# LPDDR3.net
KiCad netlist of a schematic drawn in Altium Designer
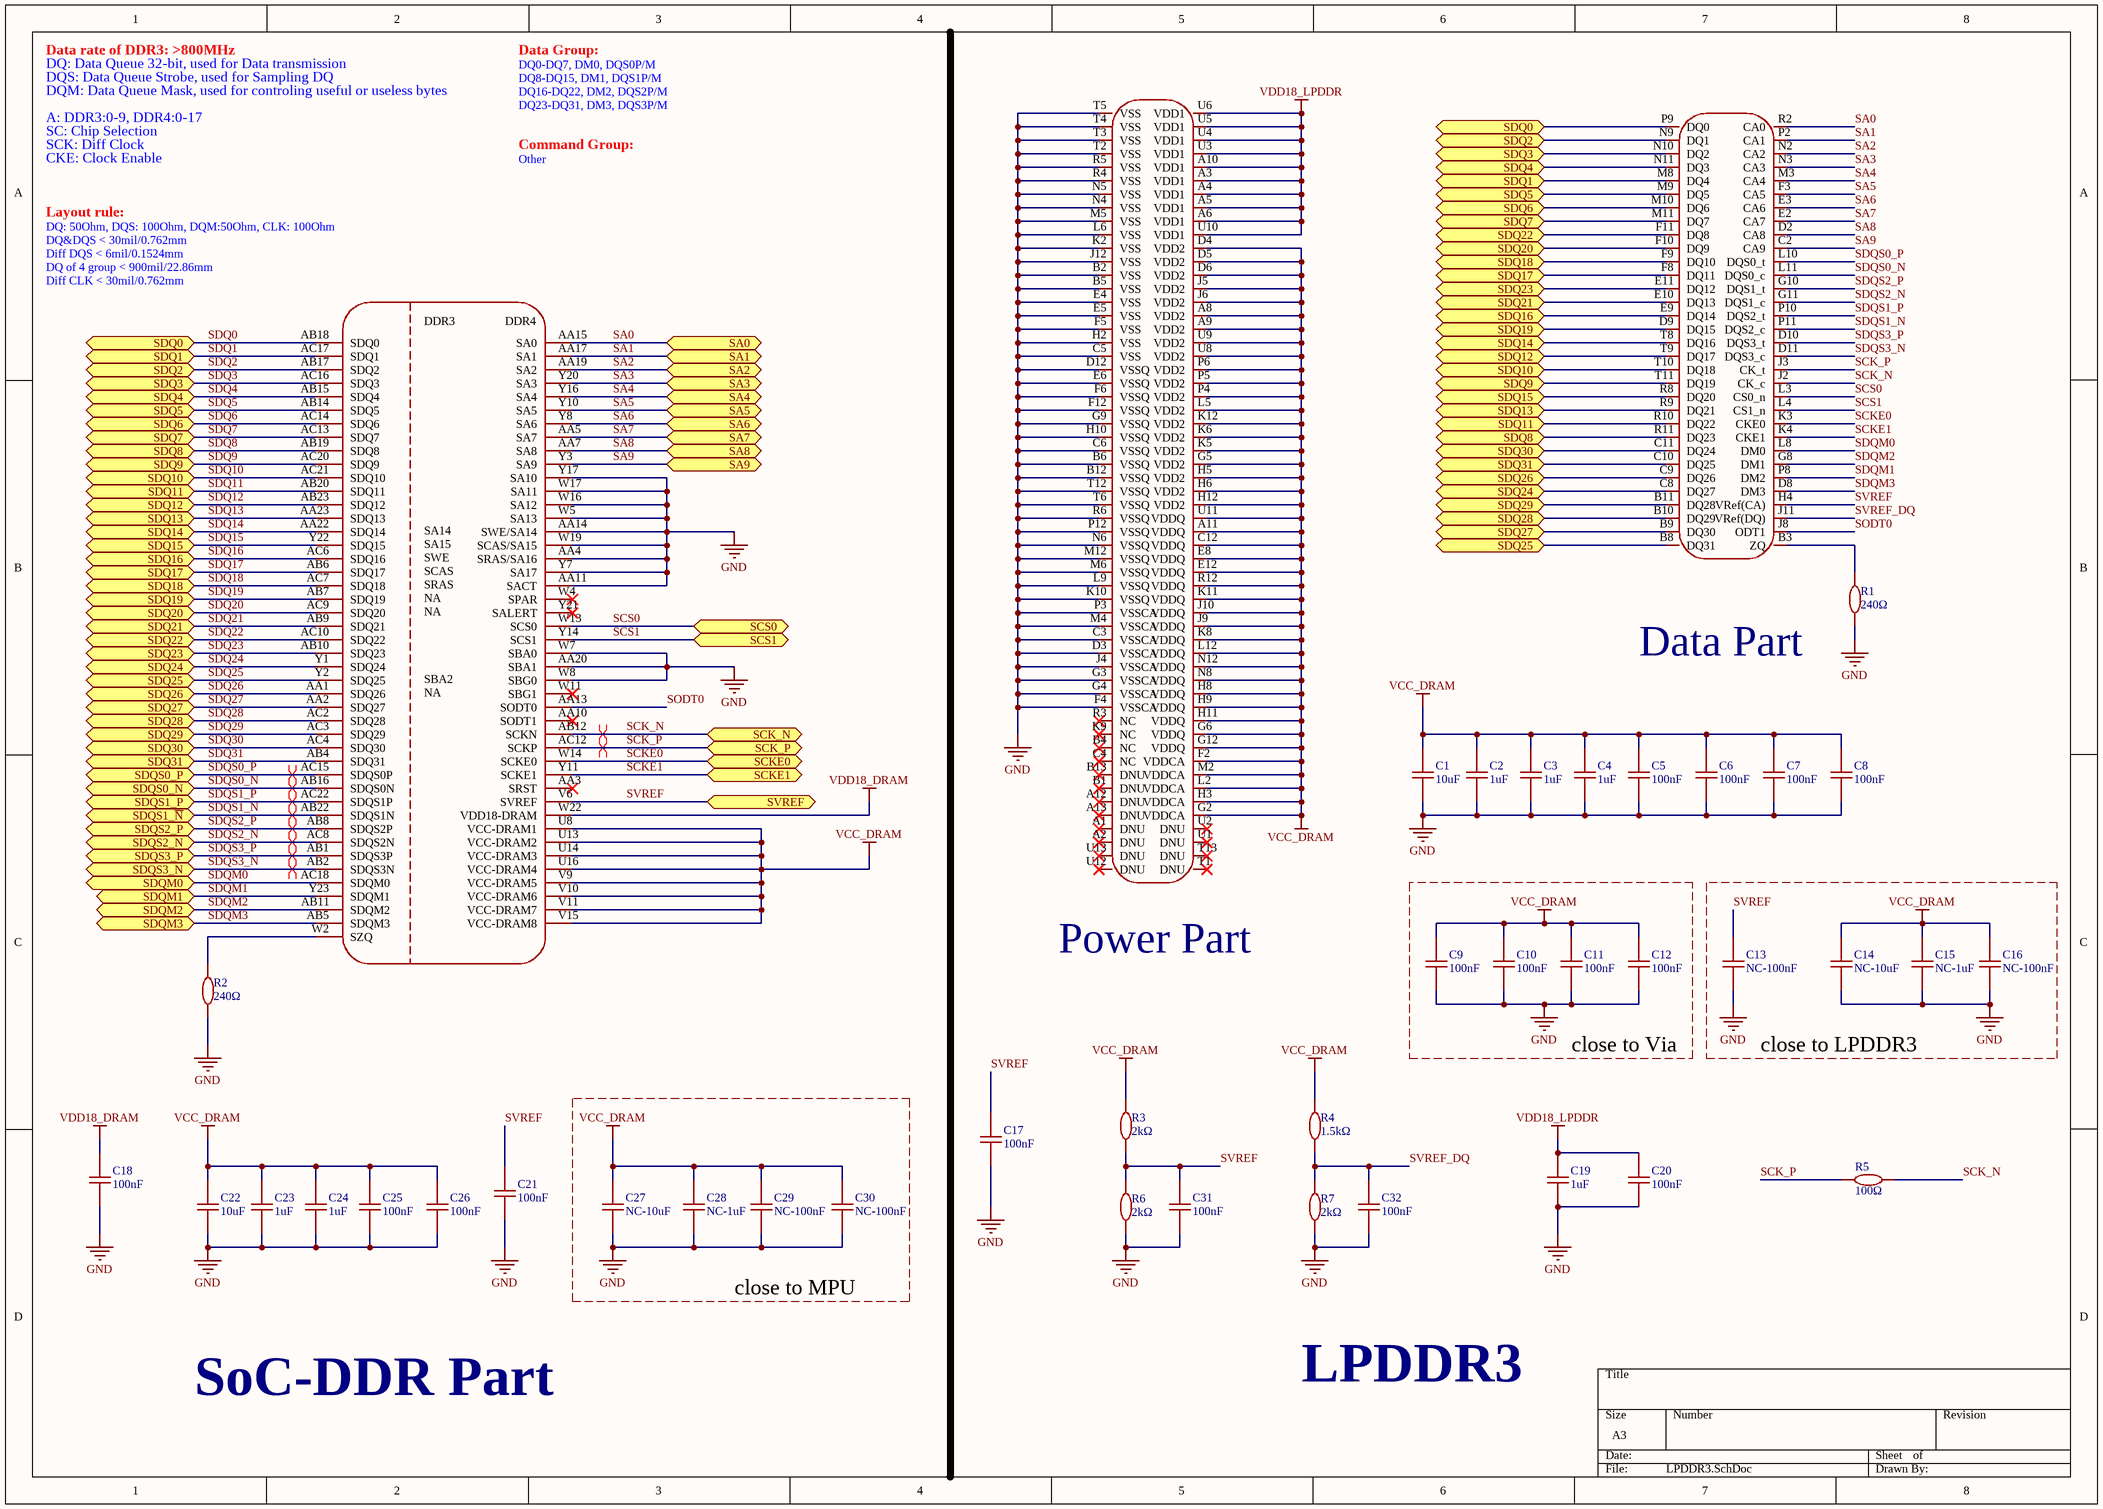
[diagram p0: LPDDR3.SchDoc]

(export (version "E")
  (design (tool "Eeschema 10.0.6"))
  (components
    (comp (ref "C1")
      (value "10uF")
      (footprint "C0603")
      (description "10V 10uF X5R ±10% 0603 Ceramic Capacitors ROHS")
      (libsource (lib "RLC") (part "10uF"))
    )
    (comp (ref "C2")
      (value "1uF")
      (footprint "C0402")
      (description "50V 1uF X5R ±10% 0603 Ceramic Capacitors ROHS")
      (libsource (lib "RLC") (part "1uF"))
    )
    (comp (ref "C3")
      (value "1uF")
      (footprint "C0402")
      (description "50V 1uF X5R ±10% 0603 Ceramic Capacitors ROHS")
      (libsource (lib "RLC") (part "1uF"))
    )
    (comp (ref "C4")
      (value "1uF")
      (footprint "C0402")
      (description "50V 1uF X5R ±10% 0603 Ceramic Capacitors ROHS")
      (libsource (lib "RLC") (part "1uF"))
    )
    (comp (ref "C5")
      (value "100nF")
      (footprint "C0402")
      (description "50V 100nF X7R ±10% 0603 Ceramic Capacitors ROHS")
      (libsource (lib "RLC") (part "100nF"))
    )
    (comp (ref "C6")
      (value "100nF")
      (footprint "C0402")
      (description "50V 100nF X7R ±10% 0603 Ceramic Capacitors ROHS")
      (libsource (lib "RLC") (part "100nF"))
    )
    (comp (ref "C7")
      (value "100nF")
      (footprint "C0402")
      (description "50V 100nF X7R ±10% 0603 Ceramic Capacitors ROHS")
      (libsource (lib "RLC") (part "100nF"))
    )
    (comp (ref "C8")
      (value "100nF")
      (footprint "C0402")
      (description "50V 100nF X7R ±10% 0603 Ceramic Capacitors ROHS")
      (libsource (lib "RLC") (part "100nF"))
    )
    (comp (ref "C9")
      (value "100nF")
      (footprint "C0402")
      (description "50V 100nF X7R ±10% 0603 Ceramic Capacitors ROHS")
      (libsource (lib "RLC") (part "100nF"))
    )
    (comp (ref "C10")
      (value "100nF")
      (footprint "C0402")
      (description "50V 100nF X7R ±10% 0603 Ceramic Capacitors ROHS")
      (libsource (lib "RLC") (part "100nF"))
    )
    (comp (ref "C11")
      (value "100nF")
      (footprint "C0402")
      (description "50V 100nF X7R ±10% 0603 Ceramic Capacitors ROHS")
      (libsource (lib "RLC") (part "100nF"))
    )
    (comp (ref "C12")
      (value "100nF")
      (footprint "C0402")
      (description "50V 100nF X7R ±10% 0603 Ceramic Capacitors ROHS")
      (libsource (lib "RLC") (part "100nF"))
    )
    (comp (ref "C13")
      (value "NC-100nF")
      (footprint "C0402")
      (description "50V 100nF X7R ±10% 0603 Ceramic Capacitors ROHS")
      (libsource (lib "RLC") (part "100nF"))
    )
    (comp (ref "C14")
      (value "NC-10uF")
      (footprint "C0603")
      (description "10V 10uF X5R ±10% 0603 Ceramic Capacitors ROHS")
      (libsource (lib "RLC") (part "10uF"))
    )
    (comp (ref "C15")
      (value "NC-1uF")
      (footprint "C0402")
      (description "50V 1uF X5R ±10% 0603 Ceramic Capacitors ROHS")
      (libsource (lib "RLC") (part "1uF"))
    )
    (comp (ref "C16")
      (value "NC-100nF")
      (footprint "C0402")
      (description "50V 100nF X7R ±10% 0603 Ceramic Capacitors ROHS")
      (libsource (lib "RLC") (part "100nF"))
    )
    (comp (ref "C17")
      (value "100nF")
      (footprint "C0402")
      (description "50V 100nF X7R ±10% 0603 Ceramic Capacitors ROHS")
      (libsource (lib "RLC") (part "100nF"))
    )
    (comp (ref "C18")
      (value "100nF")
      (footprint "C0402")
      (description "50V 100nF X7R ±10% 0603 Ceramic Capacitors ROHS")
      (libsource (lib "RLC") (part "100nF"))
    )
    (comp (ref "C19")
      (value "1uF")
      (footprint "C0402")
      (description "50V 1uF X5R ±10% 0603 Ceramic Capacitors ROHS")
      (libsource (lib "RLC") (part "1uF"))
    )
    (comp (ref "C20")
      (value "100nF")
      (footprint "C0402")
      (description "50V 100nF X7R ±10% 0603 Ceramic Capacitors ROHS")
      (libsource (lib "RLC") (part "100nF"))
    )
    (comp (ref "C21")
      (value "100nF")
      (footprint "C0402")
      (description "50V 100nF X7R ±10% 0603 Ceramic Capacitors ROHS")
      (libsource (lib "RLC") (part "100nF"))
    )
    (comp (ref "C22")
      (value "10uF")
      (footprint "C0603")
      (description "10V 10uF X5R ±10% 0603 Ceramic Capacitors ROHS")
      (libsource (lib "RLC") (part "10uF"))
    )
    (comp (ref "C23")
      (value "1uF")
      (footprint "C0402")
      (description "50V 1uF X5R ±10% 0603 Ceramic Capacitors ROHS")
      (libsource (lib "RLC") (part "1uF"))
    )
    (comp (ref "C24")
      (value "1uF")
      (footprint "C0402")
      (description "50V 1uF X5R ±10% 0603 Ceramic Capacitors ROHS")
      (libsource (lib "RLC") (part "1uF"))
    )
    (comp (ref "C25")
      (value "100nF")
      (footprint "C0402")
      (description "50V 100nF X7R ±10% 0603 Ceramic Capacitors ROHS")
      (libsource (lib "RLC") (part "100nF"))
    )
    (comp (ref "C26")
      (value "100nF")
      (footprint "C0402")
      (description "50V 100nF X7R ±10% 0603 Ceramic Capacitors ROHS")
      (libsource (lib "RLC") (part "100nF"))
    )
    (comp (ref "C27")
      (value "NC-10uF")
      (footprint "C0603")
      (description "10V 10uF X5R ±10% 0603 Ceramic Capacitors ROHS")
      (libsource (lib "RLC") (part "10uF"))
    )
    (comp (ref "C28")
      (value "NC-1uF")
      (footprint "C0402")
      (description "50V 1uF X5R ±10% 0603 Ceramic Capacitors ROHS")
      (libsource (lib "RLC") (part "1uF"))
    )
    (comp (ref "C29")
      (value "NC-100nF")
      (footprint "C0402")
      (description "50V 100nF X7R ±10% 0603 Ceramic Capacitors ROHS")
      (libsource (lib "RLC") (part "100nF"))
    )
    (comp (ref "C30")
      (value "NC-100nF")
      (footprint "C0402")
      (description "50V 100nF X7R ±10% 0603 Ceramic Capacitors ROHS")
      (libsource (lib "RLC") (part "100nF"))
    )
    (comp (ref "C31")
      (value "100nF")
      (footprint "C0402")
      (description "50V 100nF X7R ±10% 0402 Ceramic Capacitors ROHS")
      (libsource (lib "RLC") (part "100nF"))
    )
    (comp (ref "C32")
      (value "100nF")
      (footprint "C0402")
      (description "50V 100nF X7R ±10% 0402 Ceramic Capacitors ROHS")
      (libsource (lib "RLC") (part "100nF"))
    )
    (comp (ref "R1")
      (value "240Ω")
      (footprint "R0402")
      (description "240Ω 62.5mW 50V ±100ppm/℃ Thick Film Resistor ±1% 0402 Chip Resistor - Surface Mount ROHS")
      (libsource (lib "RLC") (part "240Ω"))
    )
    (comp (ref "R2")
      (value "240Ω")
      (footprint "R0402")
      (description "240Ω 62.5mW 50V ±100ppm/℃ Thick Film Resistor ±1% 0402 Chip Resistor - Surface Mount ROHS")
      (libsource (lib "RLC") (part "240Ω"))
    )
    (comp (ref "R3")
      (value "2kΩ")
      (footprint "R0402")
      (description "100mW 2kΩ 75V ±100ppm/℃ Thick Film Resistor ±1% 0402 Chip Resistor - Surface Mount ROHS")
      (libsource (lib "RLC") (part "2kΩ"))
    )
    (comp (ref "R4")
      (value "1.5kΩ")
      (footprint "R0402")
      (description "62.5mW 1.5kΩ 50V ±100ppm/℃ Thick Film Resistor ±1% 0402 Chip Resistor - Surface Mount ROHS")
      (libsource (lib "RLC") (part "1.5kΩ"))
    )
    (comp (ref "R5")
      (value "100Ω")
      (footprint "R0402")
      (description "100Ω 62.5mW 50V ±100ppm/℃ Thick Film Resistor ±1% 0402 Chip Resistor - Surface Mount ROHS")
      (libsource (lib "RLC") (part "100Ω"))
    )
    (comp (ref "R6")
      (value "2kΩ")
      (footprint "R0402")
      (description "100mW 2kΩ 75V ±100ppm/℃ Thick Film Resistor ±1% 0402 Chip Resistor - Surface Mount ROHS")
      (libsource (lib "RLC") (part "2kΩ"))
    )
    (comp (ref "R7")
      (value "2kΩ")
      (footprint "R0402")
      (description "100mW 2kΩ 75V ±100ppm/℃ Thick Film Resistor ±1% 0402 Chip Resistor - Surface Mount ROHS")
      (libsource (lib "RLC") (part "2kΩ"))
    )
    (comp (ref "U1")
      (value "LPDDR3-2G")
      (footprint "FBGA-178_L11.5-W11.0_K4E6E304EC-TL")
      (fields
        (field (name "MANUFACTURER") "SAMSUNG(三星半导体)")
        (field (name "MANUFACTURER PART") "K4E6E304EC-EGCG")
      )
      (libsource (lib "IC") (part "LPDDR3-2G"))
    )
    (comp (ref "U2")
      (value "Allwinner_H6")
      (footprint "BGA451_ALLWINNER_H6")
      (libsource (lib "IC") (part "Allwinner_H6"))
    )
  )
  (nets
    (net (code "1") (name "/SA0") (class "Default")
      (node (ref "U1") (pin "R2") (pinfunction "CA0_R2") (pintype "passive"))
      (node (ref "U2") (pin "AA15") (pinfunction "SA0_AA15") (pintype "passive"))
    )
    (net (code "2") (name "/SA1") (class "Default")
      (node (ref "U1") (pin "P2") (pinfunction "CA1_P2") (pintype "passive"))
      (node (ref "U2") (pin "AA17") (pinfunction "SA1_AA17") (pintype "passive"))
    )
    (net (code "3") (name "/SA2") (class "Default")
      (node (ref "U1") (pin "N2") (pinfunction "CA2_N2") (pintype "passive"))
      (node (ref "U2") (pin "AA19") (pinfunction "SA2_AA19") (pintype "passive"))
    )
    (net (code "4") (name "/SA3") (class "Default")
      (node (ref "U1") (pin "N3") (pinfunction "CA3_N3") (pintype "passive"))
      (node (ref "U2") (pin "Y20") (pinfunction "SA3_Y20") (pintype "passive"))
    )
    (net (code "5") (name "/SA4") (class "Default")
      (node (ref "U1") (pin "M3") (pinfunction "CA4_M3") (pintype "passive"))
      (node (ref "U2") (pin "Y16") (pinfunction "SA4_Y16") (pintype "passive"))
    )
    (net (code "6") (name "/SA5") (class "Default")
      (node (ref "U1") (pin "F3") (pinfunction "CA5_F3") (pintype "passive"))
      (node (ref "U2") (pin "Y10") (pinfunction "SA5_Y10") (pintype "passive"))
    )
    (net (code "7") (name "/SA6") (class "Default")
      (node (ref "U1") (pin "E3") (pinfunction "CA6_E3") (pintype "passive"))
      (node (ref "U2") (pin "Y8") (pinfunction "SA6_Y8") (pintype "passive"))
    )
    (net (code "8") (name "/SA7") (class "Default")
      (node (ref "U1") (pin "E2") (pinfunction "CA7_E2") (pintype "passive"))
      (node (ref "U2") (pin "AA5") (pinfunction "SA7_AA5") (pintype "passive"))
    )
    (net (code "9") (name "/SA8") (class "Default")
      (node (ref "U1") (pin "D2") (pinfunction "CA8_D2") (pintype "passive"))
      (node (ref "U2") (pin "AA7") (pinfunction "SA8_AA7") (pintype "passive"))
    )
    (net (code "10") (name "/SA9") (class "Default")
      (node (ref "U1") (pin "C2") (pinfunction "CA9_C2") (pintype "passive"))
      (node (ref "U2") (pin "Y3") (pinfunction "SA9_Y3") (pintype "passive"))
    )
    (net (code "11") (name "/SCKE0") (class "Default")
      (node (ref "U1") (pin "K3") (pinfunction "CKE0_K3") (pintype "passive"))
      (node (ref "U2") (pin "W14") (pinfunction "SCKE0_W14") (pintype "passive"))
    )
    (net (code "12") (name "/SCKE1") (class "Default")
      (node (ref "U1") (pin "K4") (pinfunction "CKE1_K4") (pintype "passive"))
      (node (ref "U2") (pin "Y11") (pinfunction "SCKE1_Y11") (pintype "passive"))
    )
    (net (code "13") (name "/SCK_N") (class "Default")
      (node (ref "R5") (pin "2") (pinfunction "2_2") (pintype "passive"))
      (node (ref "U1") (pin "J2") (pinfunction "CK_c_J2") (pintype "passive"))
      (node (ref "U2") (pin "AB12") (pinfunction "SCKN_AB12") (pintype "passive"))
    )
    (net (code "14") (name "/SCK_P") (class "Default")
      (node (ref "R5") (pin "1") (pinfunction "1_1") (pintype "passive"))
      (node (ref "U1") (pin "J3") (pinfunction "CK_t_J3") (pintype "passive"))
      (node (ref "U2") (pin "AC12") (pinfunction "SCKP_AC12") (pintype "passive"))
    )
    (net (code "15") (name "/SCS0") (class "Default")
      (node (ref "U1") (pin "L3") (pinfunction "CS0_n_L3") (pintype "passive"))
      (node (ref "U2") (pin "W13") (pinfunction "SCS0_W13") (pintype "passive"))
    )
    (net (code "16") (name "/SCS1") (class "Default")
      (node (ref "U1") (pin "L4") (pinfunction "CS1_n_L4") (pintype "passive"))
      (node (ref "U2") (pin "Y14") (pinfunction "SCS1_Y14") (pintype "passive"))
    )
    (net (code "17") (name "/SDQ0") (class "Default")
      (node (ref "U1") (pin "P9") (pinfunction "DQ0_P9") (pintype "passive"))
      (node (ref "U2") (pin "AB18") (pinfunction "SDQ0_AB18") (pintype "passive"))
    )
    (net (code "18") (name "/SDQ1") (class "Default")
      (node (ref "U1") (pin "M8") (pinfunction "DQ4_M8") (pintype "passive"))
      (node (ref "U2") (pin "AC17") (pinfunction "SDQ1_AC17") (pintype "passive"))
    )
    (net (code "19") (name "/SDQ2") (class "Default")
      (node (ref "U1") (pin "N9") (pinfunction "DQ1_N9") (pintype "passive"))
      (node (ref "U2") (pin "AB17") (pinfunction "SDQ2_AB17") (pintype "passive"))
    )
    (net (code "20") (name "/SDQ3") (class "Default")
      (node (ref "U1") (pin "N10") (pinfunction "DQ2_N10") (pintype "passive"))
      (node (ref "U2") (pin "AC16") (pinfunction "SDQ3_AC16") (pintype "passive"))
    )
    (net (code "21") (name "/SDQ4") (class "Default")
      (node (ref "U1") (pin "N11") (pinfunction "DQ3_N11") (pintype "passive"))
      (node (ref "U2") (pin "AB15") (pinfunction "SDQ4_AB15") (pintype "passive"))
    )
    (net (code "22") (name "/SDQ5") (class "Default")
      (node (ref "U1") (pin "M9") (pinfunction "DQ5_M9") (pintype "passive"))
      (node (ref "U2") (pin "AB14") (pinfunction "SDQ5_AB14") (pintype "passive"))
    )
    (net (code "23") (name "/SDQ6") (class "Default")
      (node (ref "U1") (pin "M10") (pinfunction "DQ6_M10") (pintype "passive"))
      (node (ref "U2") (pin "AC14") (pinfunction "SDQ6_AC14") (pintype "passive"))
    )
    (net (code "24") (name "/SDQ7") (class "Default")
      (node (ref "U1") (pin "M11") (pinfunction "DQ7_M11") (pintype "passive"))
      (node (ref "U2") (pin "AC13") (pinfunction "SDQ7_AC13") (pintype "passive"))
    )
    (net (code "25") (name "/SDQ8") (class "Default")
      (node (ref "U1") (pin "R11") (pinfunction "DQ23_R11") (pintype "passive"))
      (node (ref "U2") (pin "AB19") (pinfunction "SDQ8_AB19") (pintype "passive"))
    )
    (net (code "26") (name "/SDQ9") (class "Default")
      (node (ref "U1") (pin "T11") (pinfunction "DQ19_T11") (pintype "passive"))
      (node (ref "U2") (pin "AC20") (pinfunction "SDQ9_AC20") (pintype "passive"))
    )
    (net (code "27") (name "/SDQ10") (class "Default")
      (node (ref "U1") (pin "T10") (pinfunction "DQ18_T10") (pintype "passive"))
      (node (ref "U2") (pin "AC21") (pinfunction "SDQ10_AC21") (pintype "passive"))
    )
    (net (code "28") (name "/SDQ11") (class "Default")
      (node (ref "U1") (pin "R10") (pinfunction "DQ22_R10") (pintype "passive"))
      (node (ref "U2") (pin "AB20") (pinfunction "SDQ11_AB20") (pintype "passive"))
    )
    (net (code "29") (name "/SDQ12") (class "Default")
      (node (ref "U1") (pin "T9") (pinfunction "DQ17_T9") (pintype "passive"))
      (node (ref "U2") (pin "AB23") (pinfunction "SDQ12_AB23") (pintype "passive"))
    )
    (net (code "30") (name "/SDQ13") (class "Default")
      (node (ref "U1") (pin "R9") (pinfunction "DQ21_R9") (pintype "passive"))
      (node (ref "U2") (pin "AA23") (pinfunction "SDQ13_AA23") (pintype "passive"))
    )
    (net (code "31") (name "/SDQ14") (class "Default")
      (node (ref "U1") (pin "T8") (pinfunction "DQ16_T8") (pintype "passive"))
      (node (ref "U2") (pin "AA22") (pinfunction "SDQ14_AA22") (pintype "passive"))
    )
    (net (code "32") (name "/SDQ15") (class "Default")
      (node (ref "U1") (pin "R8") (pinfunction "DQ20_R8") (pintype "passive"))
      (node (ref "U2") (pin "Y22") (pinfunction "SDQ15_Y22") (pintype "passive"))
    )
    (net (code "33") (name "/SDQ16") (class "Default")
      (node (ref "U1") (pin "E9") (pinfunction "DQ14_E9") (pintype "passive"))
      (node (ref "U2") (pin "AC6") (pinfunction "SDQ16_AC6") (pintype "passive"))
    )
    (net (code "34") (name "/SDQ17") (class "Default")
      (node (ref "U1") (pin "F8") (pinfunction "DQ11_F8") (pintype "passive"))
      (node (ref "U2") (pin "AB6") (pinfunction "SDQ17_AB6") (pintype "passive"))
    )
    (net (code "35") (name "/SDQ18") (class "Default")
      (node (ref "U1") (pin "F9") (pinfunction "DQ10_F9") (pintype "passive"))
      (node (ref "U2") (pin "AC7") (pinfunction "SDQ18_AC7") (pintype "passive"))
    )
    (net (code "36") (name "/SDQ19") (class "Default")
      (node (ref "U1") (pin "D9") (pinfunction "DQ15_D9") (pintype "passive"))
      (node (ref "U2") (pin "AB7") (pinfunction "SDQ19_AB7") (pintype "passive"))
    )
    (net (code "37") (name "/SDQ20") (class "Default")
      (node (ref "U1") (pin "F10") (pinfunction "DQ9_F10") (pintype "passive"))
      (node (ref "U2") (pin "AC9") (pinfunction "SDQ20_AC9") (pintype "passive"))
    )
    (net (code "38") (name "/SDQ21") (class "Default")
      (node (ref "U1") (pin "E10") (pinfunction "DQ13_E10") (pintype "passive"))
      (node (ref "U2") (pin "AB9") (pinfunction "SDQ21_AB9") (pintype "passive"))
    )
    (net (code "39") (name "/SDQ22") (class "Default")
      (node (ref "U1") (pin "F11") (pinfunction "DQ8_F11") (pintype "passive"))
      (node (ref "U2") (pin "AC10") (pinfunction "SDQ22_AC10") (pintype "passive"))
    )
    (net (code "40") (name "/SDQ23") (class "Default")
      (node (ref "U1") (pin "E11") (pinfunction "DQ12_E11") (pintype "passive"))
      (node (ref "U2") (pin "AB10") (pinfunction "SDQ23_AB10") (pintype "passive"))
    )
    (net (code "41") (name "/SDQ24") (class "Default")
      (node (ref "U1") (pin "C8") (pinfunction "DQ27_C8") (pintype "passive"))
      (node (ref "U2") (pin "Y1") (pinfunction "SDQ24_Y1") (pintype "passive"))
    )
    (net (code "42") (name "/SDQ25") (class "Default")
      (node (ref "U1") (pin "B8") (pinfunction "DQ31_B8") (pintype "passive"))
      (node (ref "U2") (pin "Y2") (pinfunction "SDQ25_Y2") (pintype "passive"))
    )
    (net (code "43") (name "/SDQ26") (class "Default")
      (node (ref "U1") (pin "C9") (pinfunction "DQ26_C9") (pintype "passive"))
      (node (ref "U2") (pin "AA1") (pinfunction "SDQ26_AA1") (pintype "passive"))
    )
    (net (code "44") (name "/SDQ27") (class "Default")
      (node (ref "U1") (pin "B9") (pinfunction "DQ30_B9") (pintype "passive"))
      (node (ref "U2") (pin "AA2") (pinfunction "SDQ27_AA2") (pintype "passive"))
    )
    (net (code "45") (name "/SDQ28") (class "Default")
      (node (ref "U1") (pin "B10") (pinfunction "DQ29_B10") (pintype "passive"))
      (node (ref "U2") (pin "AC2") (pinfunction "SDQ28_AC2") (pintype "passive"))
    )
    (net (code "46") (name "/SDQ29") (class "Default")
      (node (ref "U1") (pin "B11") (pinfunction "DQ28_B11") (pintype "passive"))
      (node (ref "U2") (pin "AC3") (pinfunction "SDQ29_AC3") (pintype "passive"))
    )
    (net (code "47") (name "/SDQ30") (class "Default")
      (node (ref "U1") (pin "C11") (pinfunction "DQ24_C11") (pintype "passive"))
      (node (ref "U2") (pin "AC4") (pinfunction "SDQ30_AC4") (pintype "passive"))
    )
    (net (code "48") (name "/SDQ31") (class "Default")
      (node (ref "U1") (pin "C10") (pinfunction "DQ25_C10") (pintype "passive"))
      (node (ref "U2") (pin "AB4") (pinfunction "SDQ31_AB4") (pintype "passive"))
    )
    (net (code "49") (name "/SDQM0") (class "Default")
      (node (ref "U1") (pin "L8") (pinfunction "DM0_L8") (pintype "passive"))
      (node (ref "U2") (pin "AC18") (pinfunction "SDQM0_AC18") (pintype "passive"))
    )
    (net (code "50") (name "/SDQM1") (class "Default")
      (node (ref "U1") (pin "P8") (pinfunction "DM2_P8") (pintype "passive"))
      (node (ref "U2") (pin "Y23") (pinfunction "SDQM1_Y23") (pintype "passive"))
    )
    (net (code "51") (name "/SDQM2") (class "Default")
      (node (ref "U1") (pin "G8") (pinfunction "DM1_G8") (pintype "passive"))
      (node (ref "U2") (pin "AB11") (pinfunction "SDQM2_AB11") (pintype "passive"))
    )
    (net (code "52") (name "/SDQM3") (class "Default")
      (node (ref "U1") (pin "D8") (pinfunction "DM3_D8") (pintype "passive"))
      (node (ref "U2") (pin "AB5") (pinfunction "SDQM3_AB5") (pintype "passive"))
    )
    (net (code "53") (name "/SDQS0_N") (class "Default")
      (node (ref "U1") (pin "L11") (pinfunction "DQS0_c_L11") (pintype "passive"))
      (node (ref "U2") (pin "AB16") (pinfunction "SDQS0N_AB16") (pintype "passive"))
    )
    (net (code "54") (name "/SDQS0_P") (class "Default")
      (node (ref "U1") (pin "L10") (pinfunction "DQS0_t_L10") (pintype "passive"))
      (node (ref "U2") (pin "AC15") (pinfunction "SDQS0P_AC15") (pintype "passive"))
    )
    (net (code "55") (name "/SDQS1_N") (class "Default")
      (node (ref "U1") (pin "P11") (pinfunction "DQS2_c_P11") (pintype "passive"))
      (node (ref "U2") (pin "AB22") (pinfunction "SDQS1N_AB22") (pintype "passive"))
    )
    (net (code "56") (name "/SDQS1_P") (class "Default")
      (node (ref "U1") (pin "P10") (pinfunction "DQS2_t_P10") (pintype "passive"))
      (node (ref "U2") (pin "AC22") (pinfunction "SDQS1P_AC22") (pintype "passive"))
    )
    (net (code "57") (name "/SDQS2_N") (class "Default")
      (node (ref "U1") (pin "G11") (pinfunction "DQS1_c_G11") (pintype "passive"))
      (node (ref "U2") (pin "AC8") (pinfunction "SDQS2N_AC8") (pintype "passive"))
    )
    (net (code "58") (name "/SDQS2_P") (class "Default")
      (node (ref "U1") (pin "G10") (pinfunction "DQS1_t_G10") (pintype "passive"))
      (node (ref "U2") (pin "AB8") (pinfunction "SDQS2P_AB8") (pintype "passive"))
    )
    (net (code "59") (name "/SDQS3_N") (class "Default")
      (node (ref "U1") (pin "D11") (pinfunction "DQS3_c_D11") (pintype "passive"))
      (node (ref "U2") (pin "AB2") (pinfunction "SDQS3N_AB2") (pintype "passive"))
    )
    (net (code "60") (name "/SDQS3_P") (class "Default")
      (node (ref "U1") (pin "D10") (pinfunction "DQS3_t_D10") (pintype "passive"))
      (node (ref "U2") (pin "AB1") (pinfunction "SDQS3P_AB1") (pintype "passive"))
    )
    (net (code "61") (name "/SODT0") (class "Default")
      (node (ref "U1") (pin "J8") (pinfunction "ODT1_J8") (pintype "passive"))
      (node (ref "U2") (pin "AA13") (pinfunction "SODT0_AA13") (pintype "passive"))
    )
    (net (code "62") (name "/SVREF") (class "Default")
      (node (ref "C13") (pin "2") (pinfunction "2_2") (pintype "passive"))
      (node (ref "C17") (pin "2") (pinfunction "2_2") (pintype "passive"))
      (node (ref "C21") (pin "2") (pinfunction "2_2") (pintype "passive"))
      (node (ref "C31") (pin "2") (pinfunction "2_2") (pintype "passive"))
      (node (ref "R3") (pin "1") (pinfunction "1_1") (pintype "passive"))
      (node (ref "R6") (pin "2") (pinfunction "2_2") (pintype "passive"))
      (node (ref "U1") (pin "H4") (pinfunction "VRef(CA)_H4") (pintype "passive"))
      (node (ref "U2") (pin "V6") (pinfunction "SVREF_V6") (pintype "passive"))
    )
    (net (code "63") (name "/SVREF_DQ") (class "Default")
      (node (ref "C32") (pin "2") (pinfunction "2_2") (pintype "passive"))
      (node (ref "R4") (pin "1") (pinfunction "1_1") (pintype "passive"))
      (node (ref "R7") (pin "2") (pinfunction "2_2") (pintype "passive"))
      (node (ref "U1") (pin "J11") (pinfunction "VRef(DQ)_J11") (pintype "passive"))
    )
    (net (code "64") (name "GND") (class "Default")
      (node (ref "C1") (pin "1") (pinfunction "1_1") (pintype "passive"))
      (node (ref "C10") (pin "1") (pinfunction "1_1") (pintype "passive"))
      (node (ref "C11") (pin "1") (pinfunction "1_1") (pintype "passive"))
      (node (ref "C12") (pin "1") (pinfunction "1_1") (pintype "passive"))
      (node (ref "C13") (pin "1") (pinfunction "1_1") (pintype "passive"))
      (node (ref "C14") (pin "1") (pinfunction "1_1") (pintype "passive"))
      (node (ref "C15") (pin "1") (pinfunction "1_1") (pintype "passive"))
      (node (ref "C16") (pin "1") (pinfunction "1_1") (pintype "passive"))
      (node (ref "C17") (pin "1") (pinfunction "1_1") (pintype "passive"))
      (node (ref "C18") (pin "1") (pinfunction "1_1") (pintype "passive"))
      (node (ref "C19") (pin "1") (pinfunction "1_1") (pintype "passive"))
      (node (ref "C2") (pin "1") (pinfunction "1_1") (pintype "passive"))
      (node (ref "C20") (pin "1") (pinfunction "1_1") (pintype "passive"))
      (node (ref "C21") (pin "1") (pinfunction "1_1") (pintype "passive"))
      (node (ref "C22") (pin "1") (pinfunction "1_1") (pintype "passive"))
      (node (ref "C23") (pin "1") (pinfunction "1_1") (pintype "passive"))
      (node (ref "C24") (pin "1") (pinfunction "1_1") (pintype "passive"))
      (node (ref "C25") (pin "1") (pinfunction "1_1") (pintype "passive"))
      (node (ref "C26") (pin "1") (pinfunction "1_1") (pintype "passive"))
      (node (ref "C27") (pin "1") (pinfunction "1_1") (pintype "passive"))
      (node (ref "C28") (pin "1") (pinfunction "1_1") (pintype "passive"))
      (node (ref "C29") (pin "1") (pinfunction "1_1") (pintype "passive"))
      (node (ref "C3") (pin "1") (pinfunction "1_1") (pintype "passive"))
      (node (ref "C30") (pin "1") (pinfunction "1_1") (pintype "passive"))
      (node (ref "C31") (pin "1") (pinfunction "1_1") (pintype "passive"))
      (node (ref "C32") (pin "1") (pinfunction "1_1") (pintype "passive"))
      (node (ref "C4") (pin "1") (pinfunction "1_1") (pintype "passive"))
      (node (ref "C5") (pin "1") (pinfunction "1_1") (pintype "passive"))
      (node (ref "C6") (pin "1") (pinfunction "1_1") (pintype "passive"))
      (node (ref "C7") (pin "1") (pinfunction "1_1") (pintype "passive"))
      (node (ref "C8") (pin "1") (pinfunction "1_1") (pintype "passive"))
      (node (ref "C9") (pin "1") (pinfunction "1_1") (pintype "passive"))
      (node (ref "R1") (pin "1") (pinfunction "1_1") (pintype "passive"))
      (node (ref "R2") (pin "1") (pinfunction "1_1") (pintype "passive"))
      (node (ref "R6") (pin "1") (pinfunction "1_1") (pintype "passive"))
      (node (ref "R7") (pin "1") (pinfunction "1_1") (pintype "passive"))
      (node (ref "U1") (pin "B12") (pinfunction "VSSQ_B12") (pintype "passive"))
      (node (ref "U1") (pin "B2") (pinfunction "VSS_B2") (pintype "passive"))
      (node (ref "U1") (pin "B5") (pinfunction "VSS_B5") (pintype "passive"))
      (node (ref "U1") (pin "B6") (pinfunction "VSSQ_B6") (pintype "passive"))
      (node (ref "U1") (pin "C3") (pinfunction "VSSCA_C3") (pintype "passive"))
      (node (ref "U1") (pin "C5") (pinfunction "VSS_C5") (pintype "passive"))
      (node (ref "U1") (pin "C6") (pinfunction "VSSQ_C6") (pintype "passive"))
      (node (ref "U1") (pin "D12") (pinfunction "VSSQ_D12") (pintype "passive"))
      (node (ref "U1") (pin "D3") (pinfunction "VSSCA_D3") (pintype "passive"))
      (node (ref "U1") (pin "E4") (pinfunction "VSS_E4") (pintype "passive"))
      (node (ref "U1") (pin "E5") (pinfunction "VSS_E5") (pintype "passive"))
      (node (ref "U1") (pin "E6") (pinfunction "VSSQ_E6") (pintype "passive"))
      (node (ref "U1") (pin "F12") (pinfunction "VSSQ_F12") (pintype "passive"))
      (node (ref "U1") (pin "F4") (pinfunction "VSSCA_F4") (pintype "passive"))
      (node (ref "U1") (pin "F5") (pinfunction "VSS_F5") (pintype "passive"))
      (node (ref "U1") (pin "F6") (pinfunction "VSSQ_F6") (pintype "passive"))
      (node (ref "U1") (pin "G3") (pinfunction "VSSCA_G3") (pintype "passive"))
      (node (ref "U1") (pin "G4") (pinfunction "VSSCA_G4") (pintype "passive"))
      (node (ref "U1") (pin "G9") (pinfunction "VSSQ_G9") (pintype "passive"))
      (node (ref "U1") (pin "H10") (pinfunction "VSSQ_H10") (pintype "passive"))
      (node (ref "U1") (pin "H2") (pinfunction "VSS_H2") (pintype "passive"))
      (node (ref "U1") (pin "J12") (pinfunction "VSS_J12") (pintype "passive"))
      (node (ref "U1") (pin "J4") (pinfunction "VSSCA_J4") (pintype "passive"))
      (node (ref "U1") (pin "K10") (pinfunction "VSSQ_K10") (pintype "passive"))
      (node (ref "U1") (pin "K2") (pinfunction "VSS_K2") (pintype "passive"))
      (node (ref "U1") (pin "L6") (pinfunction "VSS_L6") (pintype "passive"))
      (node (ref "U1") (pin "L9") (pinfunction "VSSQ_L9") (pintype "passive"))
      (node (ref "U1") (pin "M12") (pinfunction "VSSQ_M12") (pintype "passive"))
      (node (ref "U1") (pin "M4") (pinfunction "VSSCA_M4") (pintype "passive"))
      (node (ref "U1") (pin "M5") (pinfunction "VSS_M5") (pintype "passive"))
      (node (ref "U1") (pin "M6") (pinfunction "VSSQ_M6") (pintype "passive"))
      (node (ref "U1") (pin "N4") (pinfunction "VSS_N4") (pintype "passive"))
      (node (ref "U1") (pin "N5") (pinfunction "VSS_N5") (pintype "passive"))
      (node (ref "U1") (pin "N6") (pinfunction "VSSQ_N6") (pintype "passive"))
      (node (ref "U1") (pin "P12") (pinfunction "VSSQ_P12") (pintype "passive"))
      (node (ref "U1") (pin "P3") (pinfunction "VSSCA_P3") (pintype "passive"))
      (node (ref "U1") (pin "R4") (pinfunction "VSS_R4") (pintype "passive"))
      (node (ref "U1") (pin "R5") (pinfunction "VSS_R5") (pintype "passive"))
      (node (ref "U1") (pin "R6") (pinfunction "VSSQ_R6") (pintype "passive"))
      (node (ref "U1") (pin "T12") (pinfunction "VSSQ_T12") (pintype "passive"))
      (node (ref "U1") (pin "T2") (pinfunction "VSS_T2") (pintype "passive"))
      (node (ref "U1") (pin "T3") (pinfunction "VSS_T3") (pintype "passive"))
      (node (ref "U1") (pin "T4") (pinfunction "VSS_T4") (pintype "passive"))
      (node (ref "U1") (pin "T5") (pinfunction "VSS_T5") (pintype "passive"))
      (node (ref "U1") (pin "T6") (pinfunction "VSSQ_T6") (pintype "passive"))
      (node (ref "U2") (pin "AA11") (pinfunction "SACT_AA11") (pintype "passive"))
      (node (ref "U2") (pin "AA14") (pinfunction "SWE/SA14_AA14") (pintype "passive"))
      (node (ref "U2") (pin "AA20") (pinfunction "SBA1_AA20") (pintype "passive"))
      (node (ref "U2") (pin "AA4") (pinfunction "SRAS/SA16_AA4") (pintype "passive"))
      (node (ref "U2") (pin "W16") (pinfunction "SA12_W16") (pintype "passive"))
      (node (ref "U2") (pin "W17") (pinfunction "SA11_W17") (pintype "passive"))
      (node (ref "U2") (pin "W19") (pinfunction "SCAS/SA15_W19") (pintype "passive"))
      (node (ref "U2") (pin "W5") (pinfunction "SA13_W5") (pintype "passive"))
      (node (ref "U2") (pin "W7") (pinfunction "SBA0_W7") (pintype "passive"))
      (node (ref "U2") (pin "W8") (pinfunction "SBG0_W8") (pintype "passive"))
      (node (ref "U2") (pin "Y17") (pinfunction "SA10_Y17") (pintype "passive"))
      (node (ref "U2") (pin "Y7") (pinfunction "SA17_Y7") (pintype "passive"))
    )
    (net (code "65") (name "Net-(U1B-ZQ)") (class "Default")
      (node (ref "R1") (pin "2") (pinfunction "2_2") (pintype "passive"))
      (node (ref "U1") (pin "B3") (pinfunction "ZQ_B3") (pintype "passive"))
    )
    (net (code "66") (name "Net-(U2A-SZQ)") (class "Default")
      (node (ref "R2") (pin "2") (pinfunction "2_2") (pintype "passive"))
      (node (ref "U2") (pin "W2") (pinfunction "SZQ_W2") (pintype "passive"))
    )
    (net (code "67") (name "VCC_DRAM") (class "Default")
      (node (ref "C1") (pin "2") (pinfunction "2_2") (pintype "passive"))
      (node (ref "C10") (pin "2") (pinfunction "2_2") (pintype "passive"))
      (node (ref "C11") (pin "2") (pinfunction "2_2") (pintype "passive"))
      (node (ref "C12") (pin "2") (pinfunction "2_2") (pintype "passive"))
      (node (ref "C14") (pin "2") (pinfunction "2_2") (pintype "passive"))
      (node (ref "C15") (pin "2") (pinfunction "2_2") (pintype "passive"))
      (node (ref "C16") (pin "2") (pinfunction "2_2") (pintype "passive"))
      (node (ref "C2") (pin "2") (pinfunction "2_2") (pintype "passive"))
      (node (ref "C22") (pin "2") (pinfunction "2_2") (pintype "passive"))
      (node (ref "C23") (pin "2") (pinfunction "2_2") (pintype "passive"))
      (node (ref "C24") (pin "2") (pinfunction "2_2") (pintype "passive"))
      (node (ref "C25") (pin "2") (pinfunction "2_2") (pintype "passive"))
      (node (ref "C26") (pin "2") (pinfunction "2_2") (pintype "passive"))
      (node (ref "C27") (pin "2") (pinfunction "2_2") (pintype "passive"))
      (node (ref "C28") (pin "2") (pinfunction "2_2") (pintype "passive"))
      (node (ref "C29") (pin "2") (pinfunction "2_2") (pintype "passive"))
      (node (ref "C3") (pin "2") (pinfunction "2_2") (pintype "passive"))
      (node (ref "C30") (pin "2") (pinfunction "2_2") (pintype "passive"))
      (node (ref "C4") (pin "2") (pinfunction "2_2") (pintype "passive"))
      (node (ref "C5") (pin "2") (pinfunction "2_2") (pintype "passive"))
      (node (ref "C6") (pin "2") (pinfunction "2_2") (pintype "passive"))
      (node (ref "C7") (pin "2") (pinfunction "2_2") (pintype "passive"))
      (node (ref "C8") (pin "2") (pinfunction "2_2") (pintype "passive"))
      (node (ref "C9") (pin "2") (pinfunction "2_2") (pintype "passive"))
      (node (ref "R3") (pin "2") (pinfunction "2_2") (pintype "passive"))
      (node (ref "R4") (pin "2") (pinfunction "2_2") (pintype "passive"))
      (node (ref "U1") (pin "A11") (pinfunction "VDDQ_A11") (pintype "passive"))
      (node (ref "U1") (pin "A8") (pinfunction "VDD2_A8") (pintype "passive"))
      (node (ref "U1") (pin "A9") (pinfunction "VDD2_A9") (pintype "passive"))
      (node (ref "U1") (pin "C12") (pinfunction "VDDQ_C12") (pintype "passive"))
      (node (ref "U1") (pin "D4") (pinfunction "VDD2_D4") (pintype "passive"))
      (node (ref "U1") (pin "D5") (pinfunction "VDD2_D5") (pintype "passive"))
      (node (ref "U1") (pin "D6") (pinfunction "VDD2_D6") (pintype "passive"))
      (node (ref "U1") (pin "E12") (pinfunction "VDDQ_E12") (pintype "passive"))
      (node (ref "U1") (pin "E8") (pinfunction "VDDQ_E8") (pintype "passive"))
      (node (ref "U1") (pin "F2") (pinfunction "VDDCA_F2") (pintype "passive"))
      (node (ref "U1") (pin "G12") (pinfunction "VDDQ_G12") (pintype "passive"))
      (node (ref "U1") (pin "G2") (pinfunction "VDDCA_G2") (pintype "passive"))
      (node (ref "U1") (pin "G5") (pinfunction "VDD2_G5") (pintype "passive"))
      (node (ref "U1") (pin "G6") (pinfunction "VDDQ_G6") (pintype "passive"))
      (node (ref "U1") (pin "H11") (pinfunction "VDDQ_H11") (pintype "passive"))
      (node (ref "U1") (pin "H12") (pinfunction "VDD2_H12") (pintype "passive"))
      (node (ref "U1") (pin "H3") (pinfunction "VDDCA_H3") (pintype "passive"))
      (node (ref "U1") (pin "H5") (pinfunction "VDD2_H5") (pintype "passive"))
      (node (ref "U1") (pin "H6") (pinfunction "VDD2_H6") (pintype "passive"))
      (node (ref "U1") (pin "H8") (pinfunction "VDDQ_H8") (pintype "passive"))
      (node (ref "U1") (pin "H9") (pinfunction "VDDQ_H9") (pintype "passive"))
      (node (ref "U1") (pin "J10") (pinfunction "VDDQ_J10") (pintype "passive"))
      (node (ref "U1") (pin "J5") (pinfunction "VDD2_J5") (pintype "passive"))
      (node (ref "U1") (pin "J6") (pinfunction "VDD2_J6") (pintype "passive"))
      (node (ref "U1") (pin "J9") (pinfunction "VDDQ_J9") (pintype "passive"))
      (node (ref "U1") (pin "K11") (pinfunction "VDDQ_K11") (pintype "passive"))
      (node (ref "U1") (pin "K12") (pinfunction "VDD2_K12") (pintype "passive"))
      (node (ref "U1") (pin "K5") (pinfunction "VDD2_K5") (pintype "passive"))
      (node (ref "U1") (pin "K6") (pinfunction "VDD2_K6") (pintype "passive"))
      (node (ref "U1") (pin "K8") (pinfunction "VDDQ_K8") (pintype "passive"))
      (node (ref "U1") (pin "L12") (pinfunction "VDDQ_L12") (pintype "passive"))
      (node (ref "U1") (pin "L2") (pinfunction "VDDCA_L2") (pintype "passive"))
      (node (ref "U1") (pin "L5") (pinfunction "VDD2_L5") (pintype "passive"))
      (node (ref "U1") (pin "M2") (pinfunction "VDDCA_M2") (pintype "passive"))
      (node (ref "U1") (pin "N12") (pinfunction "VDDQ_N12") (pintype "passive"))
      (node (ref "U1") (pin "N8") (pinfunction "VDDQ_N8") (pintype "passive"))
      (node (ref "U1") (pin "P4") (pinfunction "VDD2_P4") (pintype "passive"))
      (node (ref "U1") (pin "P5") (pinfunction "VDD2_P5") (pintype "passive"))
      (node (ref "U1") (pin "P6") (pinfunction "VDD2_P6") (pintype "passive"))
      (node (ref "U1") (pin "R12") (pinfunction "VDDQ_R12") (pintype "passive"))
      (node (ref "U1") (pin "U11") (pinfunction "VDDQ_U11") (pintype "passive"))
      (node (ref "U1") (pin "U8") (pinfunction "VDD2_U8") (pintype "passive"))
      (node (ref "U1") (pin "U9") (pinfunction "VDD2_U9") (pintype "passive"))
      (node (ref "U2") (pin "U13") (pinfunction "VCC-DRAM2_U13") (pintype "passive"))
      (node (ref "U2") (pin "U14") (pinfunction "VCC-DRAM3_U14") (pintype "passive"))
      (node (ref "U2") (pin "U16") (pinfunction "VCC-DRAM4_U16") (pintype "passive"))
      (node (ref "U2") (pin "U8") (pinfunction "VCC-DRAM1_U8") (pintype "passive"))
      (node (ref "U2") (pin "V10") (pinfunction "VCC-DRAM6_V10") (pintype "passive"))
      (node (ref "U2") (pin "V11") (pinfunction "VCC-DRAM7_V11") (pintype "passive"))
      (node (ref "U2") (pin "V15") (pinfunction "VCC-DRAM8_V15") (pintype "passive"))
      (node (ref "U2") (pin "V9") (pinfunction "VCC-DRAM5_V9") (pintype "passive"))
    )
    (net (code "68") (name "VDD18_DRAM") (class "Default")
      (node (ref "C18") (pin "2") (pinfunction "2_2") (pintype "passive"))
      (node (ref "U2") (pin "W22") (pinfunction "VDD18-DRAM_W22") (pintype "passive"))
    )
    (net (code "69") (name "VDD18_LPDDR") (class "Default")
      (node (ref "C19") (pin "2") (pinfunction "2_2") (pintype "passive"))
      (node (ref "C20") (pin "2") (pinfunction "2_2") (pintype "passive"))
      (node (ref "U1") (pin "A10") (pinfunction "VDD1_A10") (pintype "passive"))
      (node (ref "U1") (pin "A3") (pinfunction "VDD1_A3") (pintype "passive"))
      (node (ref "U1") (pin "A4") (pinfunction "VDD1_A4") (pintype "passive"))
      (node (ref "U1") (pin "A5") (pinfunction "VDD1_A5") (pintype "passive"))
      (node (ref "U1") (pin "A6") (pinfunction "VDD1_A6") (pintype "passive"))
      (node (ref "U1") (pin "U10") (pinfunction "VDD1_U10") (pintype "passive"))
      (node (ref "U1") (pin "U3") (pinfunction "VDD1_U3") (pintype "passive"))
      (node (ref "U1") (pin "U4") (pinfunction "VDD1_U4") (pintype "passive"))
      (node (ref "U1") (pin "U5") (pinfunction "VDD1_U5") (pintype "passive"))
      (node (ref "U1") (pin "U6") (pinfunction "VDD1_U6") (pintype "passive"))
    )
    (net (code "70") (name "unconnected-(U1A-DNU-PadA1)") (class "Default")
      (node (ref "U1") (pin "A1") (pinfunction "DNU_A1") (pintype "passive+no_connect"))
    )
    (net (code "71") (name "unconnected-(U1A-DNU-PadA2)") (class "Default")
      (node (ref "U1") (pin "A2") (pinfunction "DNU_A2") (pintype "passive+no_connect"))
    )
    (net (code "72") (name "unconnected-(U1A-DNU-PadA12)") (class "Default")
      (node (ref "U1") (pin "A12") (pinfunction "DNU_A12") (pintype "passive+no_connect"))
    )
    (net (code "73") (name "unconnected-(U1A-DNU-PadA13)") (class "Default")
      (node (ref "U1") (pin "A13") (pinfunction "DNU_A13") (pintype "passive+no_connect"))
    )
    (net (code "74") (name "unconnected-(U1A-DNU-PadB1)") (class "Default")
      (node (ref "U1") (pin "B1") (pinfunction "DNU_B1") (pintype "passive+no_connect"))
    )
    (net (code "75") (name "unconnected-(U1A-DNU-PadB13)") (class "Default")
      (node (ref "U1") (pin "B13") (pinfunction "DNU_B13") (pintype "passive+no_connect"))
    )
    (net (code "76") (name "unconnected-(U1A-DNU-PadT1)") (class "Default")
      (node (ref "U1") (pin "T1") (pinfunction "DNU_T1") (pintype "passive+no_connect"))
    )
    (net (code "77") (name "unconnected-(U1A-DNU-PadT13)") (class "Default")
      (node (ref "U1") (pin "T13") (pinfunction "DNU_T13") (pintype "passive+no_connect"))
    )
    (net (code "78") (name "unconnected-(U1A-DNU-PadU1)") (class "Default")
      (node (ref "U1") (pin "U1") (pinfunction "DNU_U1") (pintype "passive+no_connect"))
    )
    (net (code "79") (name "unconnected-(U1A-DNU-PadU2)") (class "Default")
      (node (ref "U1") (pin "U2") (pinfunction "DNU_U2") (pintype "passive+no_connect"))
    )
    (net (code "80") (name "unconnected-(U1A-DNU-PadU12)") (class "Default")
      (node (ref "U1") (pin "U12") (pinfunction "DNU_U12") (pintype "passive+no_connect"))
    )
    (net (code "81") (name "unconnected-(U1A-DNU-PadU13)") (class "Default")
      (node (ref "U1") (pin "U13") (pinfunction "DNU_U13") (pintype "passive+no_connect"))
    )
    (net (code "82") (name "unconnected-(U1A-NC-PadB4)") (class "Default")
      (node (ref "U1") (pin "B4") (pinfunction "NC_B4") (pintype "passive+no_connect"))
    )
    (net (code "83") (name "unconnected-(U1A-NC-PadC4)") (class "Default")
      (node (ref "U1") (pin "C4") (pinfunction "NC_C4") (pintype "passive+no_connect"))
    )
    (net (code "84") (name "unconnected-(U1A-NC-PadK9)") (class "Default")
      (node (ref "U1") (pin "K9") (pinfunction "NC_K9") (pintype "passive+no_connect"))
    )
    (net (code "85") (name "unconnected-(U1A-NC-PadR3)") (class "Default")
      (node (ref "U1") (pin "R3") (pinfunction "NC_R3") (pintype "passive+no_connect"))
    )
    (net (code "86") (name "unconnected-(U2A-SALERT-PadY21)") (class "Default")
      (node (ref "U2") (pin "Y21") (pinfunction "SALERT_Y21") (pintype "passive+no_connect"))
    )
    (net (code "87") (name "unconnected-(U2A-SBG1-PadW11)") (class "Default")
      (node (ref "U2") (pin "W11") (pinfunction "SBG1_W11") (pintype "passive+no_connect"))
    )
    (net (code "88") (name "unconnected-(U2A-SODT1-PadAA10)") (class "Default")
      (node (ref "U2") (pin "AA10") (pinfunction "SODT1_AA10") (pintype "passive+no_connect"))
    )
    (net (code "89") (name "unconnected-(U2A-SPAR-PadW4)") (class "Default")
      (node (ref "U2") (pin "W4") (pinfunction "SPAR_W4") (pintype "passive+no_connect"))
    )
    (net (code "90") (name "unconnected-(U2A-SRST-PadAA3)") (class "Default")
      (node (ref "U2") (pin "AA3") (pinfunction "SRST_AA3") (pintype "passive+no_connect"))
    )
  )
)
